# usb_connector.net
KiCad netlist of a schematic drawn in Altium Designer
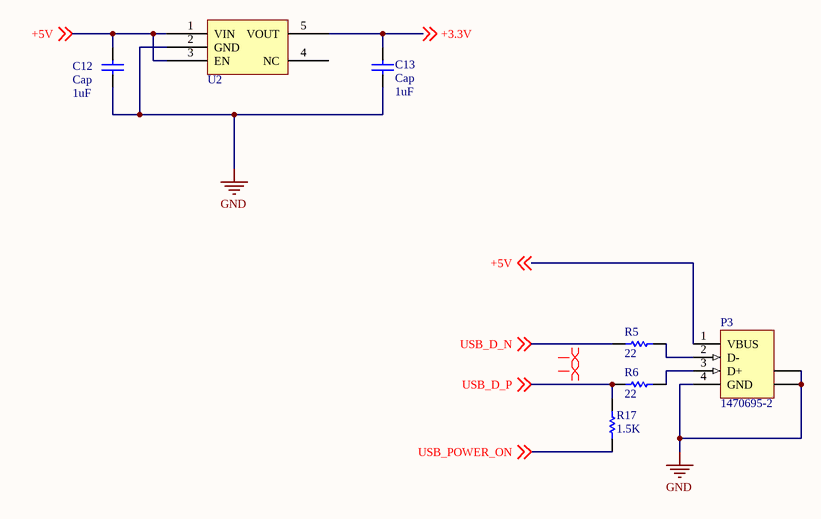
[diagram p0: usb_connector.SchDoc]

(export (version "E")
  (design (tool "Eeschema 10.0.6"))
  (components
    (comp (ref "C12")
      (value "Cap")
      (footprint "CHIP0402")
      (description "Capacitor")
      (fields (field (name "ALTIUM_VALUE") "1uF") (field (name "PUBLISHER") "Altium Limited"))
      (libsource (lib "Miscellaneous Devices") (part "Cap"))
    )
    (comp (ref "C13")
      (value "Cap")
      (footprint "CHIP0402")
      (description "Capacitor")
      (fields (field (name "ALTIUM_VALUE") "1uF") (field (name "PUBLISHER") "Altium Limited"))
      (libsource (lib "Miscellaneous Devices") (part "Cap"))
    )
    (comp (ref "P3")
      (value "1470695-2")
      (footprint "1470695A")
      (description "USB 1.1, Right Angle, SMT, A Type, Plug, 4 Position, Natural")
      (fields (field (name "PUBLISHER") "Altium Limited"))
      (libsource (lib "AMP Serial Bus USB") (part "1470695-2"))
    )
    (comp (ref "R5")
      (value "22")
      (footprint "CHIP0402")
      (description "Resistor")
      (fields (field (name "PUBLISHER") "Altium Limited"))
      (libsource (lib "Miscellaneous Devices") (part "Res1"))
    )
    (comp (ref "R6")
      (value "22")
      (footprint "CHIP0402")
      (description "Resistor")
      (fields (field (name "PUBLISHER") "Altium Limited"))
      (libsource (lib "Miscellaneous Devices") (part "Res1"))
    )
    (comp (ref "R17")
      (value "1.5K")
      (footprint "CHIP0402")
      (description "Resistor")
      (fields (field (name "PUBLISHER") "Altium Limited"))
      (libsource (lib "Miscellaneous Devices") (part "Res1"))
    )
    (comp (ref "U2")
      (value "ADP120")
      (footprint "SOT95P280X110-5L")
      (libsource (lib "mil01") (part "ADP120"))
    )
  )
  (nets
    (net (code "1") (name "+3.3V") (class "Default")
      (node (ref "C13") (pin "2") (pinfunction "2_2") (pintype "passive"))
      (node (ref "U2") (pin "5") (pinfunction "VOUT_5") (pintype "passive"))
    )
    (net (code "2") (name "+5V") (class "Default")
      (node (ref "C12") (pin "2") (pinfunction "2_2") (pintype "passive"))
      (node (ref "P3") (pin "1") (pinfunction "VBUS_1") (pintype "power_in"))
      (node (ref "U2") (pin "1") (pinfunction "VIN_1") (pintype "passive"))
      (node (ref "U2") (pin "3") (pinfunction "EN_3") (pintype "passive"))
    )
    (net (code "3") (name "GND") (class "Default")
      (node (ref "C12") (pin "1") (pinfunction "1_1") (pintype "passive"))
      (node (ref "C13") (pin "1") (pinfunction "1_1") (pintype "passive"))
      (node (ref "P3") (pin "4") (pinfunction "GND_4") (pintype "power_in"))
      (node (ref "P3") (pin "5") (pinfunction "SHLD_5") (pintype "passive"))
      (node (ref "P3") (pin "6") (pinfunction "SHLD_6") (pintype "passive"))
      (node (ref "U2") (pin "2") (pinfunction "GND_2") (pintype "passive"))
    )
    (net (code "4") (name "Net-(P3-D+)") (class "Default")
      (node (ref "P3") (pin "3") (pinfunction "D+_3") (pintype "input"))
      (node (ref "R6") (pin "2") (pinfunction "2_2") (pintype "passive"))
    )
    (net (code "5") (name "Net-(P3-D-)") (class "Default")
      (node (ref "P3") (pin "2") (pinfunction "D-_2") (pintype "input"))
      (node (ref "R5") (pin "2") (pinfunction "2_2") (pintype "passive"))
    )
    (net (code "6") (name "USB_D_N") (class "Default")
      (node (ref "R5") (pin "1") (pinfunction "1_1") (pintype "passive"))
    )
    (net (code "7") (name "USB_D_P") (class "Default")
      (node (ref "R17") (pin "1") (pinfunction "1_1") (pintype "passive"))
      (node (ref "R6") (pin "1") (pinfunction "1_1") (pintype "passive"))
    )
    (net (code "8") (name "USB_POWER_ON") (class "Default")
      (node (ref "R17") (pin "2") (pinfunction "2_2") (pintype "passive"))
    )
    (net (code "9") (name "unconnected-(U2-NC-Pad4)") (class "Default")
      (node (ref "U2") (pin "4") (pinfunction "NC_4") (pintype "passive"))
    )
  )
)
